# power_supplies.net
KiCad netlist of a schematic drawn in Altium Designer
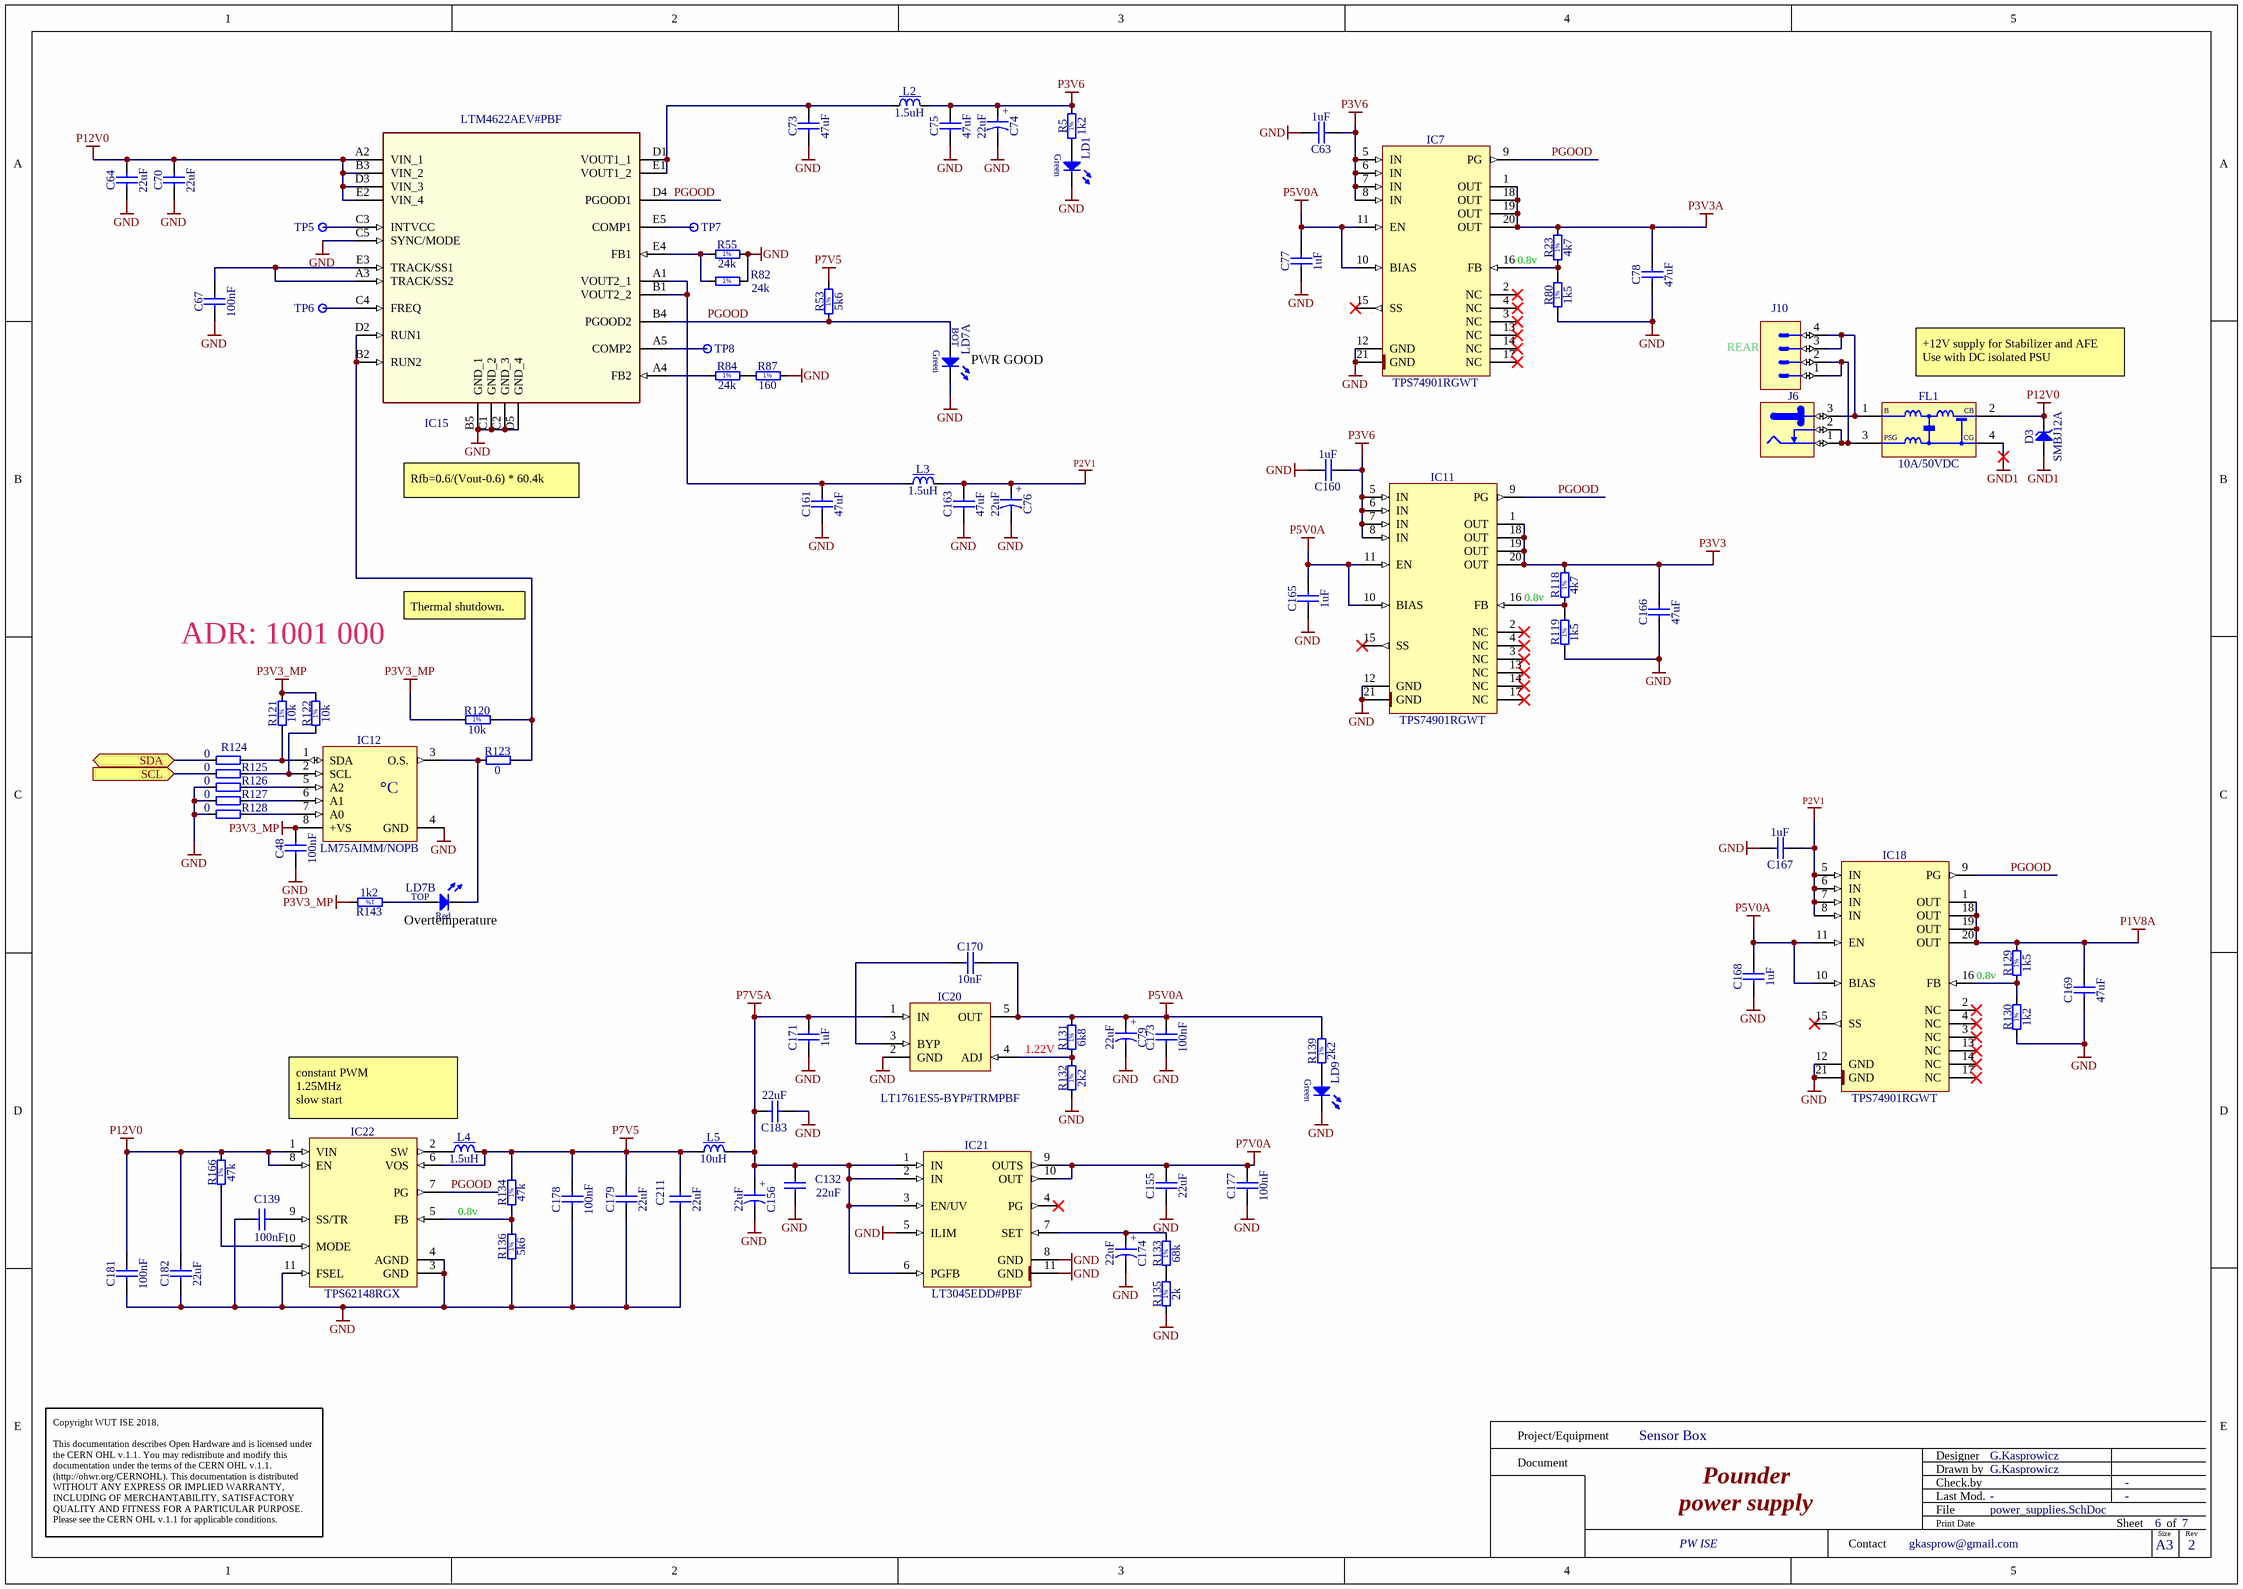
[diagram p0: power_supplies.SchDoc]

(export (version "E")
  (design (tool "Eeschema 10.0.6"))
  (components
    (comp (ref "C48")
      (value "100nF")
      (footprint "CAPC1005X55N")
      (description "Non-polarised capacitor")
      (fields (field (name "PART NUMBER") "CC0402_100NF_16V_10%_X5R") (field (name "VOLTAGE") "16V"))
      (libsource (lib "Capacitors") (part "Capacitor - non polarized"))
    )
    (comp (ref "C63")
      (value "1uF")
      (footprint "CAPC1005X55N")
      (description "Non-polarised capacitor")
      (fields (field (name "PART NUMBER") "CC0402_1UF_16V_10%_X5R") (field (name "VOLTAGE") "16V"))
      (libsource (lib "Capacitors") (part "Capacitor - non polarized"))
    )
    (comp (ref "C64")
      (value "22uF")
      (footprint "CAPC2012X135N")
      (description "Non-polarised capacitor")
      (fields (field (name "PART NUMBER") "CC0805_22UF_16V_10%_X5R") (field (name "VOLTAGE") "16V"))
      (libsource (lib "Capacitors") (part "Capacitor - non polarized"))
    )
    (comp (ref "C67")
      (value "100nF")
      (footprint "CAPC1005X55N")
      (description "Non-polarised capacitor")
      (fields (field (name "PART NUMBER") "CC0402_100NF_16V_10%_X5R") (field (name "VOLTAGE") "16V"))
      (libsource (lib "Capacitors") (part "Capacitor - non polarized"))
    )
    (comp (ref "C70")
      (value "22uF")
      (footprint "CAPC2012X135N")
      (description "Non-polarised capacitor")
      (fields (field (name "PART NUMBER") "CC0805_22UF_16V_10%_X5R") (field (name "VOLTAGE") "16V"))
      (libsource (lib "Capacitors") (part "Capacitor - non polarized"))
    )
    (comp (ref "C73")
      (value "47uF")
      (footprint "CAPC3225X270N")
      (description "Non-polarised capacitor")
      (fields (field (name "PART NUMBER") "CC1210_47UF_10V_20%_X5R") (field (name "VOLTAGE") "10V"))
      (libsource (lib "Capacitors") (part "Capacitor - non polarized"))
    )
    (comp (ref "C74")
      (value "22uF")
      (footprint "CAPMP3528X210N")
      (description "Polarised capacitor")
      (fields (field (name "PART NUMBER") "CTE3528-21_22UF_10V_10%_LESR0700") (field (name "VOLTAGE") "10V"))
      (libsource (lib "Capacitors") (part "Capacitor - polarized"))
    )
    (comp (ref "C75")
      (value "47uF")
      (footprint "CAPC3225X270N")
      (description "Non-polarised capacitor")
      (fields (field (name "PART NUMBER") "CC1210_47UF_10V_20%_X5R") (field (name "VOLTAGE") "10V"))
      (libsource (lib "Capacitors") (part "Capacitor - non polarized"))
    )
    (comp (ref "C76")
      (value "22uF")
      (footprint "CAPMP3528X210N")
      (description "Polarised capacitor")
      (fields (field (name "PART NUMBER") "CTE3528-21_22UF_10V_10%_LESR0700") (field (name "VOLTAGE") "10V"))
      (libsource (lib "Capacitors") (part "Capacitor - polarized"))
    )
    (comp (ref "C77")
      (value "1uF")
      (footprint "CAPC1005X55N")
      (description "Non-polarised capacitor")
      (fields (field (name "PART NUMBER") "CC0402_1UF_16V_10%_X5R") (field (name "VOLTAGE") "16V"))
      (libsource (lib "Capacitors") (part "Capacitor - non polarized"))
    )
    (comp (ref "C78")
      (value "47uF")
      (footprint "CAPC3225X270N")
      (description "Non-polarised capacitor")
      (fields (field (name "PART NUMBER") "CC1210_47UF_10V_20%_X5R") (field (name "VOLTAGE") "10V"))
      (libsource (lib "Capacitors") (part "Capacitor - non polarized"))
    )
    (comp (ref "C79")
      (value "22uF")
      (footprint "CAPMP3528X210N")
      (description "Polarised capacitor")
      (fields (field (name "PART NUMBER") "CTE3528-21_22UF_10V_10%_LESR0700") (field (name "VOLTAGE") "10V"))
      (libsource (lib "Capacitors") (part "Capacitor - polarized"))
    )
    (comp (ref "C132")
      (value "22uF")
      (footprint "CAPC2012X135N")
      (description "Non-polarised capacitor")
      (fields (field (name "PART NUMBER") "CC0805_22UF_16V_10%_X5R") (field (name "VOLTAGE") "16V"))
      (libsource (lib "Capacitors") (part "Capacitor - non polarized"))
    )
    (comp (ref "C139")
      (value "100nF")
      (footprint "CAPC1005X55N")
      (description "Non-polarised capacitor")
      (fields (field (name "PART NUMBER") "CC0402_100NF_16V_10%_X5R") (field (name "VOLTAGE") "16V"))
      (libsource (lib "Capacitors") (part "Capacitor - non polarized"))
    )
    (comp (ref "C155")
      (value "22uF")
      (footprint "CAPC2012X135N")
      (description "Non-polarised capacitor")
      (fields (field (name "PART NUMBER") "CC0805_22UF_16V_10%_X5R") (field (name "VOLTAGE") "16V"))
      (libsource (lib "Capacitors") (part "Capacitor - non polarized"))
    )
    (comp (ref "C156")
      (value "22uF")
      (footprint "CAPMP3528X210N")
      (description "Polarised capacitor")
      (fields (field (name "PART NUMBER") "CTE3528-21_22UF_10V_10%_LESR0700") (field (name "VOLTAGE") "10V"))
      (libsource (lib "Capacitors") (part "Capacitor - polarized"))
    )
    (comp (ref "C160")
      (value "1uF")
      (footprint "CAPC1005X55N")
      (description "Non-polarised capacitor")
      (fields (field (name "PART NUMBER") "CC0402_1UF_16V_10%_X5R") (field (name "VOLTAGE") "16V"))
      (libsource (lib "Capacitors") (part "Capacitor - non polarized"))
    )
    (comp (ref "C161")
      (value "47uF")
      (footprint "CAPC3225X270N")
      (description "Non-polarised capacitor")
      (fields (field (name "PART NUMBER") "CC1210_47UF_10V_20%_X5R") (field (name "VOLTAGE") "10V"))
      (libsource (lib "Capacitors") (part "Capacitor - non polarized"))
    )
    (comp (ref "C163")
      (value "47uF")
      (footprint "CAPC3225X270N")
      (description "Non-polarised capacitor")
      (fields (field (name "PART NUMBER") "CC1210_47UF_10V_20%_X5R") (field (name "VOLTAGE") "10V"))
      (libsource (lib "Capacitors") (part "Capacitor - non polarized"))
    )
    (comp (ref "C165")
      (value "1uF")
      (footprint "CAPC1005X55N")
      (description "Non-polarised capacitor")
      (fields (field (name "PART NUMBER") "CC0402_1UF_16V_10%_X5R") (field (name "VOLTAGE") "16V"))
      (libsource (lib "Capacitors") (part "Capacitor - non polarized"))
    )
    (comp (ref "C166")
      (value "47uF")
      (footprint "CAPC3225X270N")
      (description "Non-polarised capacitor")
      (fields (field (name "PART NUMBER") "CC1210_47UF_10V_20%_X5R") (field (name "VOLTAGE") "10V"))
      (libsource (lib "Capacitors") (part "Capacitor - non polarized"))
    )
    (comp (ref "C167")
      (value "1uF")
      (footprint "CAPC1005X55N")
      (description "Non-polarised capacitor")
      (fields (field (name "PART NUMBER") "CC0402_1UF_16V_10%_X5R") (field (name "VOLTAGE") "16V"))
      (libsource (lib "Capacitors") (part "Capacitor - non polarized"))
    )
    (comp (ref "C168")
      (value "1uF")
      (footprint "CAPC1005X55N")
      (description "Non-polarised capacitor")
      (fields (field (name "PART NUMBER") "CC0402_1UF_16V_10%_X5R") (field (name "VOLTAGE") "16V"))
      (libsource (lib "Capacitors") (part "Capacitor - non polarized"))
    )
    (comp (ref "C169")
      (value "47uF")
      (footprint "CAPC3225X270N")
      (description "Non-polarised capacitor")
      (fields (field (name "PART NUMBER") "CC1210_47UF_10V_20%_X5R") (field (name "VOLTAGE") "10V"))
      (libsource (lib "Capacitors") (part "Capacitor - non polarized"))
    )
    (comp (ref "C170")
      (value "10nF")
      (footprint "CAPC1005X55N")
      (description "Non-polarised capacitor")
      (fields (field (name "PART NUMBER") "CC0402_10NF_16V_10%_X7R") (field (name "VOLTAGE") "16V"))
      (libsource (lib "Capacitors") (part "Capacitor - non polarized"))
    )
    (comp (ref "C171")
      (value "1uF")
      (footprint "CAPC1005X55N")
      (description "Non-polarised capacitor")
      (fields (field (name "PART NUMBER") "CC0402_1UF_16V_10%_X5R") (field (name "VOLTAGE") "16V"))
      (libsource (lib "Capacitors") (part "Capacitor - non polarized"))
    )
    (comp (ref "C173")
      (value "100nF")
      (footprint "CAPC1005X55N")
      (description "Non-polarised capacitor")
      (fields (field (name "PART NUMBER") "CC0402_100NF_16V_10%_X5R") (field (name "VOLTAGE") "16V"))
      (libsource (lib "Capacitors") (part "Capacitor - non polarized"))
    )
    (comp (ref "C174")
      (value "22uF")
      (footprint "CAPMP3528X210N")
      (description "Polarised capacitor")
      (fields (field (name "PART NUMBER") "CTE3528-21_22UF_10V_10%_LESR0700") (field (name "VOLTAGE") "10V"))
      (libsource (lib "Capacitors") (part "Capacitor - polarized"))
    )
    (comp (ref "C177")
      (value "100nF")
      (footprint "CAPC1005X55N")
      (description "Non-polarised capacitor")
      (fields (field (name "PART NUMBER") "CC0402_100NF_16V_10%_X5R") (field (name "VOLTAGE") "16V"))
      (libsource (lib "Capacitors") (part "Capacitor - non polarized"))
    )
    (comp (ref "C178")
      (value "100nF")
      (footprint "CAPC1005X55N")
      (description "Non-polarised capacitor")
      (fields (field (name "PART NUMBER") "CC0402_100NF_16V_10%_X5R") (field (name "VOLTAGE") "16V"))
      (libsource (lib "Capacitors") (part "Capacitor - non polarized"))
    )
    (comp (ref "C179")
      (value "22uF")
      (footprint "CAPC2012X135N")
      (description "Non-polarised capacitor")
      (fields (field (name "PART NUMBER") "CC0805_22UF_16V_10%_X5R") (field (name "VOLTAGE") "16V"))
      (libsource (lib "Capacitors") (part "Capacitor - non polarized"))
    )
    (comp (ref "C181")
      (value "100nF")
      (footprint "CAPC1005X55N")
      (description "Non-polarised capacitor")
      (fields (field (name "PART NUMBER") "CC0402_100NF_16V_10%_X5R") (field (name "VOLTAGE") "16V"))
      (libsource (lib "Capacitors") (part "Capacitor - non polarized"))
    )
    (comp (ref "C182")
      (value "22uF")
      (footprint "CAPC2012X135N")
      (description "Non-polarised capacitor")
      (fields (field (name "PART NUMBER") "CC0805_22UF_16V_10%_X5R") (field (name "VOLTAGE") "16V"))
      (libsource (lib "Capacitors") (part "Capacitor - non polarized"))
    )
    (comp (ref "C183")
      (value "22uF")
      (footprint "CAPC2012X135N")
      (description "Non-polarised capacitor")
      (fields (field (name "PART NUMBER") "CC0805_22UF_16V_10%_X5R") (field (name "VOLTAGE") "16V"))
      (libsource (lib "Capacitors") (part "Capacitor - non polarized"))
    )
    (comp (ref "C211")
      (value "22uF")
      (footprint "CAPC2012X135N")
      (description "Non-polarised capacitor")
      (fields (field (name "PART NUMBER") "CC0805_22UF_16V_10%_X5R") (field (name "VOLTAGE") "16V"))
      (libsource (lib "Capacitors") (part "Capacitor - non polarized"))
    )
    (comp (ref "D3")
      (value "SMBJ12A")
      (footprint "DIOM5336X265N")
      (description "Zener Diode")
      (fields (field (name "VOLTAGE") "12V") (field (name "POWER") "600W"))
      (libsource (lib "ICs And Semiconductors") (part "Diode Zener"))
    )
    (comp (ref "FL1")
      (value "10A/50VDC")
      (footprint "FIL_MURATA_BNX02")
      (description "Block Type EMIFIL (LC Combined)")
      (fields (field (name "PART NUMBER") "FIL_MURATA_BNX022-01L") (field (name "MANUFACTURER") "MURATA"))
      (libsource (lib "Inductors & Transformers") (part "FIL_MURATA_BNX02"))
    )
    (comp (ref "IC7")
      (value "TPS74901RGWT")
      (footprint "QFN65P500X500X100-21N-S325")
      (description "3A, 0.8 to 3.6V Adjustable Low-Dropout Linear Regulator with Programmable Soft-Start")
      (fields (field (name "MANUFACTURER") "TEXAS INSTRUMENTS"))
      (libsource (lib "ICs And Semiconductors") (part "TPS74901RGWT"))
    )
    (comp (ref "IC11")
      (value "TPS74901RGWT")
      (footprint "QFN65P500X500X100-21N-S325")
      (description "3A, 0.8 to 3.6V Adjustable Low-Dropout Linear Regulator with Programmable Soft-Start")
      (fields (field (name "MANUFACTURER") "TEXAS INSTRUMENTS"))
      (libsource (lib "ICs And Semiconductors") (part "TPS74901RGWT"))
    )
    (comp (ref "IC12")
      (value "LM75AIMM/NOPB")
      (footprint "SOP65P490X109-8N")
      (description "Digital Temperature Sensor and Thermal Watchdog with Two-Wire Interface")
      (fields (field (name "MANUFACTURER") "TEXAS INSTRUMENTS"))
      (libsource (lib "ICs And Semiconductors") (part "LM75"))
    )
    (comp (ref "IC15")
      (value "LTM4622AEV#PBF")
      (footprint "LGA25C127P5X5_625X625X190")
      (description "Dual Ultrathin 2A or Single 4A, 3.6V to 20V, 1.5V to 12V   Step-Down DC/DC μModule Regulator")
      (fields (field (name "MANUFACTURER") "LINEAR TECHNOLOGY"))
      (libsource (lib "LIBRARY_SCH") (part "PM_LTM4622"))
    )
    (comp (ref "IC18")
      (value "TPS74901RGWT")
      (footprint "QFN65P500X500X100-21N-S325")
      (description "3A, 0.8 to 3.6V Adjustable Low-Dropout Linear Regulator with Programmable Soft-Start")
      (fields (field (name "MANUFACTURER") "TEXAS INSTRUMENTS"))
      (libsource (lib "ICs And Semiconductors") (part "TPS74901RGWT"))
    )
    (comp (ref "IC20")
      (value "LT1761ES5-BYP#TRMPBF")
      (footprint "SOT95P280X100-5N")
      (description "100mA, Low Noise, LDO Micropower Adjustable Regulator in SOT-23")
      (fields (field (name "MANUFACTURER") "LINEAR TECHNOLOGY"))
      (libsource (lib "ICs And Semiconductors") (part "LT1761-BYP"))
    )
    (comp (ref "IC21")
      (value "LT3045EDD#PBF")
      (footprint "SON50P300X300X80-11N-R175X248")
      (description "20V, 500mA, Ultralow Noise, Ultrahigh PSRR Linear Regulator")
      (fields (field (name "MANUFACTURER") "LINEAR TECHNOLOGY"))
      (libsource (lib "ICs And Semiconductors") (part "LT3045EDD"))
    )
    (comp (ref "IC22")
      (value "TPS62148RGX")
      (footprint "TEXAS_RGX0011A")
      (description "3V-17V 2A Step-Down Converter, High Accuracy, With DCS-Control")
      (fields (field (name "MANUFACTURER") "TEXAS INSTRUMENTS"))
      (libsource (lib "ICs And Semiconductors") (part "TPS62148"))
    )
    (comp (ref "J6")
      (value "Jack")
      (footprint "Library-connectors:SWITCHCRAFT_L712RA")
      (description "24V /3. 5A, 2.1mm Diameter Pin, SMD DC Power Supply Connector With  Break Contact")
      (fields (field (name "PART NUMBER") "SWITCHCRAFT_L712RA") (field (name "MANUFACTURER") "SWITCHCRAFT"))
      (libsource (lib "LIBRARY_SCH") (part "CON_DC_5A_THT_RA"))
    )
    (comp (ref "J10")
      (value "Mini-Fit Jr.™")
      (footprint "MOLEX_39-30-0040")
      (description "Connector 4 Male")
      (fields (field (name "PART NUMBER") "MOLEX_39-30-0040") (field (name "MANUFACTURER") "MOLEX"))
      (libsource (lib "Connectors") (part "Connector 4 Male"))
    )
    (comp (ref "L2")
      (value "1.5uH")
      (footprint "IND_TDK_SPM6530")
      (description "Inductor With Core")
      (fields (field (name "PART NUMBER") "IND_1.5UH_20%_TDK_SPM6530") (field (name "POWER") "11A"))
      (libsource (lib "Inductors & Transformers") (part "Inductor With Magnetic core"))
    )
    (comp (ref "L3")
      (value "1.5uH")
      (footprint "IND_TDK_SPM6530")
      (description "Inductor With Core")
      (fields (field (name "PART NUMBER") "IND_1.5UH_20%_TDK_SPM6530") (field (name "POWER") "11A"))
      (libsource (lib "Inductors & Transformers") (part "Inductor With Magnetic core"))
    )
    (comp (ref "L4")
      (value "1.5uH")
      (footprint "IND_TDK_SPM6530")
      (description "Inductor With Core")
      (fields (field (name "PART NUMBER") "IND_1.5UH_20%_TDK_SPM6530") (field (name "POWER") "11A"))
      (libsource (lib "Inductors & Transformers") (part "Inductor With Magnetic core"))
    )
    (comp (ref "L5")
      (value "10uH")
      (footprint "IND_MURATA-PS_8400")
      (description "Inductor With Core")
      (fields (field (name "PART NUMBER") "IND_10UH_10%_MURATA-PS_8400") (field (name "POWER") "950mA"))
      (libsource (lib "Inductors & Transformers") (part "Inductor With Magnetic core"))
    )
    (comp (ref "LD1")
      (value "Green")
      (footprint "LED_KINGBRIGHT_KPH-1608CGCKr")
      (description "Green 0603")
      (fields
        (field (name "PART NUMBER") "LED_KINGBRIGHT_KPH-1608CGCK")
        (field (name "MANUFACTURER") "KINGBRIGHT")
      )
      (libsource (lib "LIBRARY_SCH") (part "LED_0603_Green"))
    )
    (comp (ref "LD7")
      (value "Red/Green")
      (footprint "LED_DIALIGHT_571-0112F")
      (description "2x LED  Botom Green, Top Red")
      (fields (field (name "PART NUMBER") "LED_DIALIGHT_571-0112F") (field (name "MANUFACTURER") "DIALIGHT"))
      (libsource (lib "ICs And Semiconductors") (part "LED x2 G-1C2A-BOT_R-3C4A-TOP"))
    )
    (comp (ref "LD9")
      (value "Green")
      (footprint "LED_KINGBRIGHT_KPH-1608CGCKr")
      (description "Green 0603")
      (fields
        (field (name "PART NUMBER") "LED_KINGBRIGHT_KPH-1608CGCK")
        (field (name "MANUFACTURER") "KINGBRIGHT")
      )
      (libsource (lib "LIBRARY_SCH") (part "LED_0603_Green"))
    )
    (comp (ref "R5")
      (value "1k2")
      (footprint "RESC1608X55N")
      (description "Resistor - 1%")
      (fields (field (name "PART NUMBER") "R0603_1K2_1%_0.1W_100PPM") (field (name "POWER") "0.1W"))
      (libsource (lib "Resistors") (part "Resistor - 1%"))
    )
    (comp (ref "R23")
      (value "4k7")
      (footprint "RESC1608X55N")
      (description "Resistor - 1%")
      (fields (field (name "PART NUMBER") "R0603_4K7_1%_0.1W_100PPM") (field (name "POWER") "0.1W"))
      (libsource (lib "Resistors") (part "Resistor - 1%"))
    )
    (comp (ref "R53")
      (value "5k6")
      (footprint "RESC1608X55N")
      (description "Resistor - 1%")
      (fields (field (name "PART NUMBER") "R0603_5K6_1%_0.1W_100PPM") (field (name "POWER") "0.1W"))
      (libsource (lib "Resistors") (part "Resistor - 1%"))
    )
    (comp (ref "R55")
      (value "24k")
      (footprint "RESC1608X55N")
      (description "Resistor - 1%")
      (fields (field (name "PART NUMBER") "R0603_24K_1%_0.1W_100PPM") (field (name "POWER") "0.1W"))
      (libsource (lib "Resistors") (part "Resistor - 1%"))
    )
    (comp (ref "R80")
      (value "1k5")
      (footprint "RESC1608X55N")
      (description "Resistor - 1%")
      (fields (field (name "PART NUMBER") "R0603_1K5_1%_0.1W_100PPM") (field (name "POWER") "0.1W"))
      (libsource (lib "Resistors") (part "Resistor - 1%"))
    )
    (comp (ref "R82")
      (value "24k")
      (footprint "RESC1608X55N")
      (description "Resistor - 1%")
      (fields (field (name "PART NUMBER") "R0603_24K_1%_0.1W_100PPM") (field (name "POWER") "0.1W"))
      (libsource (lib "Resistors") (part "Resistor - 1%"))
    )
    (comp (ref "R84")
      (value "24k")
      (footprint "RESC1608X55N")
      (description "Resistor - 1%")
      (fields (field (name "PART NUMBER") "R0603_24K_1%_0.1W_100PPM") (field (name "POWER") "0.1W"))
      (libsource (lib "Resistors") (part "Resistor - 1%"))
    )
    (comp (ref "R87")
      (value "160")
      (footprint "RESC1608X55N")
      (description "Resistor - 1%")
      (fields (field (name "PART NUMBER") "R0603_160R_1%_0.1W_100PPM") (field (name "POWER") "0.1W"))
      (libsource (lib "Resistors") (part "Resistor - 1%"))
    )
    (comp (ref "R118")
      (value "4k7")
      (footprint "RESC1608X55N")
      (description "Resistor - 1%")
      (fields (field (name "PART NUMBER") "R0603_4K7_1%_0.1W_100PPM") (field (name "POWER") "0.1W"))
      (libsource (lib "Resistors") (part "Resistor - 1%"))
    )
    (comp (ref "R119")
      (value "1k5")
      (footprint "RESC1608X55N")
      (description "Resistor - 1%")
      (fields (field (name "PART NUMBER") "R0603_1K5_1%_0.1W_100PPM") (field (name "POWER") "0.1W"))
      (libsource (lib "Resistors") (part "Resistor - 1%"))
    )
    (comp (ref "R120")
      (value "10k")
      (footprint "RESC1005X40N")
      (description "Resistor - 1%")
      (fields (field (name "PART NUMBER") "R0402_10K_1%_0.0625W_100PPM") (field (name "POWER") "0.0625W"))
      (libsource (lib "Resistors") (part "Resistor - 1%"))
    )
    (comp (ref "R121")
      (value "10k")
      (footprint "RESC1005X40N")
      (description "Resistor - 1%")
      (fields (field (name "PART NUMBER") "R0402_10K_1%_0.0625W_100PPM") (field (name "POWER") "0.0625W"))
      (libsource (lib "Resistors") (part "Resistor - 1%"))
    )
    (comp (ref "R122")
      (value "10k")
      (footprint "RESC1005X40N")
      (description "Resistor - 1%")
      (fields (field (name "PART NUMBER") "R0402_10K_1%_0.0625W_100PPM") (field (name "POWER") "0.0625W"))
      (libsource (lib "Resistors") (part "Resistor - 1%"))
    )
    (comp (ref "R123")
      (value "0")
      (footprint "RESC1005X40N")
      (description "Resistor")
      (fields (field (name "PART NUMBER") "R0402_0R_JUMPER") (field (name "MANUFACTURER") "GENERIC"))
      (libsource (lib "Resistors") (part "Resistor"))
    )
    (comp (ref "R124")
      (value "0")
      (footprint "RESC1005X40N")
      (description "Resistor")
      (fields (field (name "PART NUMBER") "R0402_0R_JUMPER") (field (name "MANUFACTURER") "GENERIC"))
      (libsource (lib "Resistors") (part "Resistor"))
    )
    (comp (ref "R125")
      (value "0")
      (footprint "RESC1005X40N")
      (description "Resistor")
      (fields (field (name "PART NUMBER") "R0402_0R_JUMPER") (field (name "MANUFACTURER") "GENERIC"))
      (libsource (lib "Resistors") (part "Resistor"))
    )
    (comp (ref "R126")
      (value "0")
      (footprint "RESC1005X40N")
      (description "Resistor")
      (fields (field (name "PART NUMBER") "R0402_0R_JUMPER") (field (name "MANUFACTURER") "GENERIC"))
      (libsource (lib "Resistors") (part "Resistor"))
    )
    (comp (ref "R127")
      (value "0")
      (footprint "RESC1005X40N")
      (description "Resistor")
      (fields (field (name "PART NUMBER") "R0402_0R_JUMPER") (field (name "MANUFACTURER") "GENERIC"))
      (libsource (lib "Resistors") (part "Resistor"))
    )
    (comp (ref "R128")
      (value "0")
      (footprint "RESC1005X40N")
      (description "Resistor")
      (fields (field (name "PART NUMBER") "R0402_0R_JUMPER") (field (name "MANUFACTURER") "GENERIC"))
      (libsource (lib "Resistors") (part "Resistor"))
    )
    (comp (ref "R129")
      (value "1k5")
      (footprint "RESC1608X55N")
      (description "Resistor - 1%")
      (fields (field (name "PART NUMBER") "R0603_1K5_1%_0.1W_100PPM") (field (name "POWER") "0.1W"))
      (libsource (lib "Resistors") (part "Resistor - 1%"))
    )
    (comp (ref "R130")
      (value "1k2")
      (footprint "RESC1608X55N")
      (description "Resistor - 1%")
      (fields (field (name "PART NUMBER") "R0603_1K2_1%_0.1W_100PPM") (field (name "POWER") "0.1W"))
      (libsource (lib "Resistors") (part "Resistor - 1%"))
    )
    (comp (ref "R131")
      (value "6k8")
      (footprint "RESC1608X55N")
      (description "Resistor - 1%")
      (fields (field (name "PART NUMBER") "R0603_6K8_1%_0.1W_100PPM") (field (name "POWER") "0.1W"))
      (libsource (lib "Resistors") (part "Resistor - 1%"))
    )
    (comp (ref "R132")
      (value "2k2")
      (footprint "RESC1608X55N")
      (description "Resistor - 1%")
      (fields (field (name "PART NUMBER") "R0603_2K2_1%_0.1W_100PPM") (field (name "POWER") "0.1W"))
      (libsource (lib "Resistors") (part "Resistor - 1%"))
    )
    (comp (ref "R133")
      (value "68k")
      (footprint "RESC1005X40N")
      (description "Resistor - 1%")
      (fields (field (name "PART NUMBER") "R0402_68K_1%_0.0625W_100PPM") (field (name "POWER") "0.0625W"))
      (libsource (lib "Resistors") (part "Resistor - 1%"))
    )
    (comp (ref "R134")
      (value "47k")
      (footprint "RESC1608X55N")
      (description "Resistor - 1%")
      (fields (field (name "PART NUMBER") "R0603_47K_1%_0.1W_100PPM") (field (name "POWER") "0.1W"))
      (libsource (lib "Resistors") (part "Resistor - 1%"))
    )
    (comp (ref "R135")
      (value "2k")
      (footprint "RESC1005X40N")
      (description "Resistor - 1%")
      (fields (field (name "PART NUMBER") "R0402_2K_1%_0.0625W_100PPM") (field (name "POWER") "0.0625W"))
      (libsource (lib "Resistors") (part "Resistor - 1%"))
    )
    (comp (ref "R136")
      (value "5k6")
      (footprint "RESC1608X55N")
      (description "Resistor - 1%")
      (fields (field (name "PART NUMBER") "R0603_5K6_1%_0.1W_100PPM") (field (name "POWER") "0.1W"))
      (libsource (lib "Resistors") (part "Resistor - 1%"))
    )
    (comp (ref "R139")
      (value "2k2")
      (footprint "RESC1608X55N")
      (description "Resistor - 1%")
      (fields (field (name "PART NUMBER") "R0603_2K2_1%_0.1W_100PPM") (field (name "POWER") "0.1W"))
      (libsource (lib "Resistors") (part "Resistor - 1%"))
    )
    (comp (ref "R143")
      (value "1k2")
      (footprint "RESC1608X55N")
      (description "Resistor - 1%")
      (fields (field (name "PART NUMBER") "R0603_1K2_1%_0.1W_100PPM") (field (name "POWER") "0.1W"))
      (libsource (lib "Resistors") (part "Resistor - 1%"))
    )
    (comp (ref "R166")
      (value "47k")
      (footprint "RESC1608X55N")
      (description "Resistor - 1%")
      (fields (field (name "PART NUMBER") "R0603_47K_1%_0.1W_100PPM") (field (name "POWER") "0.1W"))
      (libsource (lib "Resistors") (part "Resistor - 1%"))
    )
    (comp (ref "TP5")
      (value "Test Point")
      (footprint "TPS127")
      (fields (field (name "PART NUMBER") "SMD_PAD_1.27X1.27MM"))
      (libsource (lib "Eletro-mechanical") (part "Test Point"))
    )
    (comp (ref "TP6")
      (value "Test Point")
      (footprint "TPS127")
      (fields (field (name "PART NUMBER") "SMD_PAD_1.27X1.27MM"))
      (libsource (lib "Eletro-mechanical") (part "Test Point"))
    )
    (comp (ref "TP7")
      (value "Test Point")
      (footprint "TPS127")
      (fields (field (name "PART NUMBER") "SMD_PAD_1.27X1.27MM"))
      (libsource (lib "Eletro-mechanical") (part "Test Point"))
    )
    (comp (ref "TP8")
      (value "Test Point")
      (footprint "TPS127")
      (fields (field (name "PART NUMBER") "SMD_PAD_1.27X1.27MM"))
      (libsource (lib "Eletro-mechanical") (part "Test Point"))
    )
  )
  (nets
    (net (code "1") (name "/PGOOD") (class "Default")
      (node (ref "IC11") (pin "9") (pinfunction "PG_9") (pintype "output"))
      (node (ref "IC15") (pin "B4") (pinfunction "PGOOD2_B4") (pintype "open_collector"))
      (node (ref "IC15") (pin "D4") (pinfunction "PGOOD1_D4") (pintype "open_collector"))
      (node (ref "IC18") (pin "9") (pinfunction "PG_9") (pintype "output"))
      (node (ref "IC22") (pin "7") (pinfunction "PG_7") (pintype "output"))
      (node (ref "IC7") (pin "9") (pinfunction "PG_9") (pintype "output"))
      (node (ref "LD7") (pin "2") (pinfunction "A_2") (pintype "passive"))
      (node (ref "R53") (pin "1") (pinfunction "1_1") (pintype "passive"))
    )
    (net (code "2") (name "/SCL") (class "Default")
      (node (ref "R125") (pin "1") (pinfunction "1_1") (pintype "passive"))
    )
    (net (code "3") (name "/SDA") (class "Default")
      (node (ref "R124") (pin "1") (pinfunction "1_1") (pintype "passive"))
    )
    (net (code "4") (name "GND") (class "Default")
      (node (ref "C132") (pin "1") (pinfunction "1_1") (pintype "passive"))
      (node (ref "C139") (pin "2") (pinfunction "2_2") (pintype "passive"))
      (node (ref "C155") (pin "1") (pinfunction "1_1") (pintype "passive"))
      (node (ref "C156") (pin "2") (pinfunction "2_2") (pintype "passive"))
      (node (ref "C160") (pin "2") (pinfunction "2_2") (pintype "passive"))
      (node (ref "C161") (pin "1") (pinfunction "1_1") (pintype "passive"))
      (node (ref "C163") (pin "1") (pinfunction "1_1") (pintype "passive"))
      (node (ref "C165") (pin "1") (pinfunction "1_1") (pintype "passive"))
      (node (ref "C166") (pin "1") (pinfunction "1_1") (pintype "passive"))
      (node (ref "C167") (pin "2") (pinfunction "2_2") (pintype "passive"))
      (node (ref "C168") (pin "1") (pinfunction "1_1") (pintype "passive"))
      (node (ref "C169") (pin "1") (pinfunction "1_1") (pintype "passive"))
      (node (ref "C171") (pin "1") (pinfunction "1_1") (pintype "passive"))
      (node (ref "C173") (pin "1") (pinfunction "1_1") (pintype "passive"))
      (node (ref "C174") (pin "2") (pinfunction "2_2") (pintype "passive"))
      (node (ref "C177") (pin "1") (pinfunction "1_1") (pintype "passive"))
      (node (ref "C178") (pin "1") (pinfunction "1_1") (pintype "passive"))
      (node (ref "C179") (pin "1") (pinfunction "1_1") (pintype "passive"))
      (node (ref "C181") (pin "1") (pinfunction "1_1") (pintype "passive"))
      (node (ref "C182") (pin "1") (pinfunction "1_1") (pintype "passive"))
      (node (ref "C183") (pin "1") (pinfunction "1_1") (pintype "passive"))
      (node (ref "C211") (pin "1") (pinfunction "1_1") (pintype "passive"))
      (node (ref "C48") (pin "1") (pinfunction "1_1") (pintype "passive"))
      (node (ref "C63") (pin "2") (pinfunction "2_2") (pintype "passive"))
      (node (ref "C64") (pin "1") (pinfunction "1_1") (pintype "passive"))
      (node (ref "C67") (pin "1") (pinfunction "1_1") (pintype "passive"))
      (node (ref "C70") (pin "1") (pinfunction "1_1") (pintype "passive"))
      (node (ref "C73") (pin "1") (pinfunction "1_1") (pintype "passive"))
      (node (ref "C74") (pin "2") (pinfunction "2_2") (pintype "passive"))
      (node (ref "C75") (pin "1") (pinfunction "1_1") (pintype "passive"))
      (node (ref "C76") (pin "2") (pinfunction "2_2") (pintype "passive"))
      (node (ref "C77") (pin "1") (pinfunction "1_1") (pintype "passive"))
      (node (ref "C78") (pin "1") (pinfunction "1_1") (pintype "passive"))
      (node (ref "C79") (pin "2") (pinfunction "2_2") (pintype "passive"))
      (node (ref "IC11") (pin "12") (pinfunction "GND_12") (pintype "power_in"))
      (node (ref "IC11") (pin "21") (pinfunction "GND_21") (pintype "power_in"))
      (node (ref "IC12") (pin "4") (pinfunction "GND_4") (pintype "power_in"))
      (node (ref "IC15") (pin "B5") (pinfunction "GND_1_B5") (pintype "power_in"))
      (node (ref "IC15") (pin "C1") (pinfunction "GND_2_C1") (pintype "power_in"))
      (node (ref "IC15") (pin "C2") (pinfunction "GND_3_C2") (pintype "power_in"))
      (node (ref "IC15") (pin "C5") (pinfunction "SYNC/MODE_C5") (pintype "input"))
      (node (ref "IC15") (pin "D5") (pinfunction "GND_4_D5") (pintype "power_in"))
      (node (ref "IC18") (pin "12") (pinfunction "GND_12") (pintype "power_in"))
      (node (ref "IC18") (pin "21") (pinfunction "GND_21") (pintype "power_in"))
      (node (ref "IC20") (pin "2") (pinfunction "GND_2") (pintype "power_in"))
      (node (ref "IC21") (pin "11") (pinfunction "GND_11") (pintype "power_in"))
      (node (ref "IC21") (pin "5") (pinfunction "ILIM_5") (pintype "input"))
      (node (ref "IC21") (pin "8") (pinfunction "GND_8") (pintype "power_in"))
      (node (ref "IC22") (pin "11") (pinfunction "FSEL_11") (pintype "input"))
      (node (ref "IC22") (pin "3") (pinfunction "GND_3") (pintype "power_in"))
      (node (ref "IC22") (pin "4") (pinfunction "AGND_4") (pintype "power_in"))
      (node (ref "IC7") (pin "12") (pinfunction "GND_12") (pintype "power_in"))
      (node (ref "IC7") (pin "21") (pinfunction "GND_21") (pintype "power_in"))
      (node (ref "LD1") (pin "1") (pinfunction "C_1") (pintype "passive"))
      (node (ref "LD7") (pin "1") (pinfunction "C_1") (pintype "passive"))
      (node (ref "LD9") (pin "1") (pinfunction "C_1") (pintype "passive"))
      (node (ref "R119") (pin "1") (pinfunction "1_1") (pintype "passive"))
      (node (ref "R126") (pin "1") (pinfunction "1_1") (pintype "passive"))
      (node (ref "R127") (pin "1") (pinfunction "1_1") (pintype "passive"))
      (node (ref "R128") (pin "1") (pinfunction "1_1") (pintype "passive"))
      (node (ref "R130") (pin "1") (pinfunction "1_1") (pintype "passive"))
      (node (ref "R132") (pin "1") (pinfunction "1_1") (pintype "passive"))
      (node (ref "R135") (pin "1") (pinfunction "1_1") (pintype "passive"))
      (node (ref "R136") (pin "1") (pinfunction "1_1") (pintype "passive"))
      (node (ref "R55") (pin "2") (pinfunction "2_2") (pintype "passive"))
      (node (ref "R80") (pin "1") (pinfunction "1_1") (pintype "passive"))
      (node (ref "R82") (pin "2") (pinfunction "2_2") (pintype "passive"))
      (node (ref "R87") (pin "2") (pinfunction "2_2") (pintype "passive"))
    )
    (net (code "5") (name "GND1") (class "Default")
      (node (ref "D3") (pin "2") (pinfunction "A_2") (pintype "passive"))
      (node (ref "FL1") (pin "4") (pinfunction "CG_4") (pintype "passive"))
    )
    (net (code "6") (name "Net-(FL1-B)") (class "Default")
      (node (ref "FL1") (pin "1") (pinfunction "B_1") (pintype "passive"))
      (node (ref "J10") (pin "3") (pinfunction "3_3") (pintype "bidirectional"))
      (node (ref "J10") (pin "4") (pinfunction "4_4") (pintype "bidirectional"))
      (node (ref "J6") (pin "3") (pinfunction "3_3") (pintype "bidirectional"))
    )
    (net (code "7") (name "Net-(FL1-PSG)") (class "Default")
      (node (ref "FL1") (pin "3") (pinfunction "PSG_3") (pintype "passive"))
      (node (ref "J10") (pin "1") (pinfunction "1_1") (pintype "bidirectional"))
      (node (ref "J10") (pin "2") (pinfunction "2_2") (pintype "bidirectional"))
      (node (ref "J6") (pin "1") (pinfunction "1_1") (pintype "bidirectional"))
      (node (ref "J6") (pin "2") (pinfunction "2_2") (pintype "bidirectional"))
    )
    (net (code "8") (name "Net-(IC7-FB)") (class "Default")
      (node (ref "IC7") (pin "16") (pinfunction "FB_16") (pintype "input"))
      (node (ref "R23") (pin "1") (pinfunction "1_1") (pintype "passive"))
      (node (ref "R80") (pin "2") (pinfunction "2_2") (pintype "passive"))
    )
    (net (code "9") (name "Net-(IC11-FB)") (class "Default")
      (node (ref "IC11") (pin "16") (pinfunction "FB_16") (pintype "input"))
      (node (ref "R118") (pin "1") (pinfunction "1_1") (pintype "passive"))
      (node (ref "R119") (pin "2") (pinfunction "2_2") (pintype "passive"))
    )
    (net (code "10") (name "Net-(IC12-A0)") (class "Default")
      (node (ref "IC12") (pin "7") (pinfunction "A0_7") (pintype "input"))
      (node (ref "R128") (pin "2") (pinfunction "2_2") (pintype "passive"))
    )
    (net (code "11") (name "Net-(IC12-A1)") (class "Default")
      (node (ref "IC12") (pin "6") (pinfunction "A1_6") (pintype "input"))
      (node (ref "R127") (pin "2") (pinfunction "2_2") (pintype "passive"))
    )
    (net (code "12") (name "Net-(IC12-A2)") (class "Default")
      (node (ref "IC12") (pin "5") (pinfunction "A2_5") (pintype "input"))
      (node (ref "R126") (pin "2") (pinfunction "2_2") (pintype "passive"))
    )
    (net (code "13") (name "Net-(IC12-O.S.)") (class "Default")
      (node (ref "IC12") (pin "3") (pinfunction "O.S._3") (pintype "output"))
      (node (ref "LD7") (pin "3") (pinfunction "C_3") (pintype "passive"))
      (node (ref "R123") (pin "1") (pinfunction "1_1") (pintype "passive"))
    )
    (net (code "14") (name "Net-(IC12-SCL)") (class "Default")
      (node (ref "IC12") (pin "2") (pinfunction "SCL_2") (pintype "input"))
      (node (ref "R122") (pin "1") (pinfunction "1_1") (pintype "passive"))
      (node (ref "R125") (pin "2") (pinfunction "2_2") (pintype "passive"))
    )
    (net (code "15") (name "Net-(IC12-SDA)") (class "Default")
      (node (ref "IC12") (pin "1") (pinfunction "SDA_1") (pintype "bidirectional"))
      (node (ref "R121") (pin "1") (pinfunction "1_1") (pintype "passive"))
      (node (ref "R124") (pin "2") (pinfunction "2_2") (pintype "passive"))
    )
    (net (code "16") (name "Net-(IC15-COMP1)") (class "Default")
      (node (ref "IC15") (pin "E5") (pinfunction "COMP1_E5") (pintype "passive"))
      (node (ref "TP7") (pin "1") (pinfunction "1_1") (pintype "bidirectional"))
    )
    (net (code "17") (name "Net-(IC15-COMP2)") (class "Default")
      (node (ref "IC15") (pin "A5") (pinfunction "COMP2_A5") (pintype "passive"))
      (node (ref "TP8") (pin "1") (pinfunction "1_1") (pintype "bidirectional"))
    )
    (net (code "18") (name "Net-(IC15-FB1)") (class "Default")
      (node (ref "IC15") (pin "E4") (pinfunction "FB1_E4") (pintype "input"))
      (node (ref "R55") (pin "1") (pinfunction "1_1") (pintype "passive"))
      (node (ref "R82") (pin "1") (pinfunction "1_1") (pintype "passive"))
    )
    (net (code "19") (name "Net-(IC15-FB2)") (class "Default")
      (node (ref "IC15") (pin "A4") (pinfunction "FB2_A4") (pintype "input"))
      (node (ref "R84") (pin "1") (pinfunction "1_1") (pintype "passive"))
    )
    (net (code "20") (name "Net-(IC15-FREQ)") (class "Default")
      (node (ref "IC15") (pin "C4") (pinfunction "FREQ_C4") (pintype "input"))
      (node (ref "TP6") (pin "1") (pinfunction "1_1") (pintype "bidirectional"))
    )
    (net (code "21") (name "Net-(IC15-INTVCC)") (class "Default")
      (node (ref "IC15") (pin "C3") (pinfunction "INTVCC_C3") (pintype "input"))
      (node (ref "TP5") (pin "1") (pinfunction "1_1") (pintype "bidirectional"))
    )
    (net (code "22") (name "Net-(IC15-RUN1)") (class "Default")
      (node (ref "IC15") (pin "B2") (pinfunction "RUN2_B2") (pintype "input"))
      (node (ref "IC15") (pin "D2") (pinfunction "RUN1_D2") (pintype "input"))
      (node (ref "R120") (pin "2") (pinfunction "2_2") (pintype "passive"))
      (node (ref "R123") (pin "2") (pinfunction "2_2") (pintype "passive"))
    )
    (net (code "23") (name "Net-(IC15-TRACK{slash}SS1)") (class "Default")
      (node (ref "C67") (pin "2") (pinfunction "2_2") (pintype "passive"))
      (node (ref "IC15") (pin "A3") (pinfunction "TRACK/SS2_A3") (pintype "input"))
      (node (ref "IC15") (pin "E3") (pinfunction "TRACK/SS1_E3") (pintype "input"))
    )
    (net (code "24") (name "Net-(IC15-VOUT1_1)") (class "Default")
      (node (ref "C73") (pin "2") (pinfunction "2_2") (pintype "passive"))
      (node (ref "IC15") (pin "D1") (pinfunction "VOUT1_1_D1") (pintype "power_in"))
      (node (ref "IC15") (pin "E1") (pinfunction "VOUT1_2_E1") (pintype "power_in"))
      (node (ref "L2") (pin "1") (pinfunction "1_1") (pintype "passive"))
    )
    (net (code "25") (name "Net-(IC15-VOUT2_1)") (class "Default")
      (node (ref "C161") (pin "2") (pinfunction "2_2") (pintype "passive"))
      (node (ref "IC15") (pin "A1") (pinfunction "VOUT2_1_A1") (pintype "power_in"))
      (node (ref "IC15") (pin "B1") (pinfunction "VOUT2_2_B1") (pintype "power_in"))
      (node (ref "L3") (pin "1") (pinfunction "1_1") (pintype "passive"))
    )
    (net (code "26") (name "Net-(IC18-FB)") (class "Default")
      (node (ref "IC18") (pin "16") (pinfunction "FB_16") (pintype "input"))
      (node (ref "R129") (pin "1") (pinfunction "1_1") (pintype "passive"))
      (node (ref "R130") (pin "2") (pinfunction "2_2") (pintype "passive"))
    )
    (net (code "27") (name "Net-(IC20-ADJ)") (class "Default")
      (node (ref "IC20") (pin "4") (pinfunction "ADJ_4") (pintype "input"))
      (node (ref "R131") (pin "1") (pinfunction "1_1") (pintype "passive"))
      (node (ref "R132") (pin "2") (pinfunction "2_2") (pintype "passive"))
    )
    (net (code "28") (name "Net-(IC20-BYP)") (class "Default")
      (node (ref "C170") (pin "1") (pinfunction "1_1") (pintype "passive"))
      (node (ref "IC20") (pin "3") (pinfunction "BYP_3") (pintype "input"))
    )
    (net (code "29") (name "Net-(IC21-SET)") (class "Default")
      (node (ref "C174") (pin "1") (pinfunction "1_1") (pintype "passive"))
      (node (ref "IC21") (pin "7") (pinfunction "SET_7") (pintype "input"))
      (node (ref "R133") (pin "2") (pinfunction "2_2") (pintype "passive"))
    )
    (net (code "30") (name "Net-(IC22-FB)") (class "Default")
      (node (ref "IC22") (pin "5") (pinfunction "FB_5") (pintype "input"))
      (node (ref "R134") (pin "1") (pinfunction "1_1") (pintype "passive"))
      (node (ref "R136") (pin "2") (pinfunction "2_2") (pintype "passive"))
    )
    (net (code "31") (name "Net-(IC22-MODE)") (class "Default")
      (node (ref "IC22") (pin "10") (pinfunction "MODE_10") (pintype "input"))
      (node (ref "R166") (pin "1") (pinfunction "1_1") (pintype "passive"))
    )
    (net (code "32") (name "Net-(IC22-SS{slash}TR)") (class "Default")
      (node (ref "C139") (pin "1") (pinfunction "1_1") (pintype "passive"))
      (node (ref "IC22") (pin "9") (pinfunction "SS/TR_9") (pintype "input"))
    )
    (net (code "33") (name "Net-(IC22-SW)") (class "Default")
      (node (ref "IC22") (pin "2") (pinfunction "SW_2") (pintype "output"))
      (node (ref "L4") (pin "1") (pinfunction "1_1") (pintype "passive"))
    )
    (net (code "34") (name "Net-(LD1-A)") (class "Default")
      (node (ref "LD1") (pin "2") (pinfunction "A_2") (pintype "passive"))
      (node (ref "R5") (pin "1") (pinfunction "1_1") (pintype "passive"))
    )
    (net (code "35") (name "Net-(LD7B-A)") (class "Default")
      (node (ref "LD7") (pin "4") (pinfunction "A_4") (pintype "passive"))
      (node (ref "R143") (pin "1") (pinfunction "1_1") (pintype "passive"))
    )
    (net (code "36") (name "Net-(LD9-A)") (class "Default")
      (node (ref "LD9") (pin "2") (pinfunction "A_2") (pintype "passive"))
      (node (ref "R139") (pin "1") (pinfunction "1_1") (pintype "passive"))
    )
    (net (code "37") (name "Net-(R84-Pad2)") (class "Default")
      (node (ref "R84") (pin "2") (pinfunction "2_2") (pintype "passive"))
      (node (ref "R87") (pin "1") (pinfunction "1_1") (pintype "passive"))
    )
    (net (code "38") (name "Net-(R133-Pad1)") (class "Default")
      (node (ref "R133") (pin "1") (pinfunction "1_1") (pintype "passive"))
      (node (ref "R135") (pin "2") (pinfunction "2_2") (pintype "passive"))
    )
    (net (code "39") (name "P1V8A") (class "Default")
      (node (ref "C169") (pin "2") (pinfunction "2_2") (pintype "passive"))
      (node (ref "IC18") (pin "1") (pinfunction "OUT_1") (pintype "power_in"))
      (node (ref "IC18") (pin "18") (pinfunction "OUT_18") (pintype "power_in"))
      (node (ref "IC18") (pin "19") (pinfunction "OUT_19") (pintype "power_in"))
      (node (ref "IC18") (pin "20") (pinfunction "OUT_20") (pintype "power_in"))
      (node (ref "R129") (pin "2") (pinfunction "2_2") (pintype "passive"))
    )
    (net (code "40") (name "P2V1") (class "Default")
      (node (ref "C163") (pin "2") (pinfunction "2_2") (pintype "passive"))
      (node (ref "C167") (pin "1") (pinfunction "1_1") (pintype "passive"))
      (node (ref "C76") (pin "1") (pinfunction "1_1") (pintype "passive"))
      (node (ref "IC18") (pin "5") (pinfunction "IN_5") (pintype "input"))
      (node (ref "IC18") (pin "6") (pinfunction "IN_6") (pintype "input"))
      (node (ref "IC18") (pin "7") (pinfunction "IN_7") (pintype "input"))
      (node (ref "IC18") (pin "8") (pinfunction "IN_8") (pintype "input"))
      (node (ref "L3") (pin "2") (pinfunction "2_2") (pintype "passive"))
    )
    (net (code "41") (name "P3V3") (class "Default")
      (node (ref "C166") (pin "2") (pinfunction "2_2") (pintype "passive"))
      (node (ref "IC11") (pin "1") (pinfunction "OUT_1") (pintype "power_in"))
      (node (ref "IC11") (pin "18") (pinfunction "OUT_18") (pintype "power_in"))
      (node (ref "IC11") (pin "19") (pinfunction "OUT_19") (pintype "power_in"))
      (node (ref "IC11") (pin "20") (pinfunction "OUT_20") (pintype "power_in"))
      (node (ref "R118") (pin "2") (pinfunction "2_2") (pintype "passive"))
    )
    (net (code "42") (name "P3V3A") (class "Default")
      (node (ref "C78") (pin "2") (pinfunction "2_2") (pintype "passive"))
      (node (ref "IC7") (pin "1") (pinfunction "OUT_1") (pintype "power_in"))
      (node (ref "IC7") (pin "18") (pinfunction "OUT_18") (pintype "power_in"))
      (node (ref "IC7") (pin "19") (pinfunction "OUT_19") (pintype "power_in"))
      (node (ref "IC7") (pin "20") (pinfunction "OUT_20") (pintype "power_in"))
      (node (ref "R23") (pin "2") (pinfunction "2_2") (pintype "passive"))
    )
    (net (code "43") (name "P3V3_MP") (class "Default")
      (node (ref "C48") (pin "2") (pinfunction "2_2") (pintype "passive"))
      (node (ref "IC12") (pin "8") (pinfunction "+VS_8") (pintype "power_in"))
      (node (ref "R120") (pin "1") (pinfunction "1_1") (pintype "passive"))
      (node (ref "R121") (pin "2") (pinfunction "2_2") (pintype "passive"))
      (node (ref "R122") (pin "2") (pinfunction "2_2") (pintype "passive"))
      (node (ref "R143") (pin "2") (pinfunction "2_2") (pintype "passive"))
    )
    (net (code "44") (name "P3V6") (class "Default")
      (node (ref "C160") (pin "1") (pinfunction "1_1") (pintype "passive"))
      (node (ref "C63") (pin "1") (pinfunction "1_1") (pintype "passive"))
      (node (ref "C74") (pin "1") (pinfunction "1_1") (pintype "passive"))
      (node (ref "C75") (pin "2") (pinfunction "2_2") (pintype "passive"))
      (node (ref "IC11") (pin "5") (pinfunction "IN_5") (pintype "input"))
      (node (ref "IC11") (pin "6") (pinfunction "IN_6") (pintype "input"))
      (node (ref "IC11") (pin "7") (pinfunction "IN_7") (pintype "input"))
      (node (ref "IC11") (pin "8") (pinfunction "IN_8") (pintype "input"))
      (node (ref "IC7") (pin "5") (pinfunction "IN_5") (pintype "input"))
      (node (ref "IC7") (pin "6") (pinfunction "IN_6") (pintype "input"))
      (node (ref "IC7") (pin "7") (pinfunction "IN_7") (pintype "input"))
      (node (ref "IC7") (pin "8") (pinfunction "IN_8") (pintype "input"))
      (node (ref "L2") (pin "2") (pinfunction "2_2") (pintype "passive"))
      (node (ref "R5") (pin "2") (pinfunction "2_2") (pintype "passive"))
    )
    (net (code "45") (name "P5V0A") (class "Default")
      (node (ref "C165") (pin "2") (pinfunction "2_2") (pintype "passive"))
      (node (ref "C168") (pin "2") (pinfunction "2_2") (pintype "passive"))
      (node (ref "C170") (pin "2") (pinfunction "2_2") (pintype "passive"))
      (node (ref "C173") (pin "2") (pinfunction "2_2") (pintype "passive"))
      (node (ref "C77") (pin "2") (pinfunction "2_2") (pintype "passive"))
      (node (ref "C79") (pin "1") (pinfunction "1_1") (pintype "passive"))
      (node (ref "IC11") (pin "10") (pinfunction "BIAS_10") (pintype "input"))
      (node (ref "IC11") (pin "11") (pinfunction "EN_11") (pintype "input"))
      (node (ref "IC18") (pin "10") (pinfunction "BIAS_10") (pintype "input"))
      (node (ref "IC18") (pin "11") (pinfunction "EN_11") (pintype "input"))
      (node (ref "IC20") (pin "5") (pinfunction "OUT_5") (pintype "power_in"))
      (node (ref "IC7") (pin "10") (pinfunction "BIAS_10") (pintype "input"))
      (node (ref "IC7") (pin "11") (pinfunction "EN_11") (pintype "input"))
      (node (ref "R131") (pin "2") (pinfunction "2_2") (pintype "passive"))
      (node (ref "R139") (pin "2") (pinfunction "2_2") (pintype "passive"))
    )
    (net (code "46") (name "P7V0A") (class "Default")
      (node (ref "C155") (pin "2") (pinfunction "2_2") (pintype "passive"))
      (node (ref "C177") (pin "2") (pinfunction "2_2") (pintype "passive"))
      (node (ref "IC21") (pin "10") (pinfunction "OUT_10") (pintype "output"))
      (node (ref "IC21") (pin "9") (pinfunction "OUTS_9") (pintype "output"))
    )
    (net (code "47") (name "P7V5") (class "Default")
      (node (ref "C178") (pin "2") (pinfunction "2_2") (pintype "passive"))
      (node (ref "C179") (pin "2") (pinfunction "2_2") (pintype "passive"))
      (node (ref "C211") (pin "2") (pinfunction "2_2") (pintype "passive"))
      (node (ref "IC22") (pin "6") (pinfunction "VOS_6") (pintype "input"))
      (node (ref "L4") (pin "2") (pinfunction "2_2") (pintype "passive"))
      (node (ref "L5") (pin "1") (pinfunction "1_1") (pintype "passive"))
      (node (ref "R134") (pin "2") (pinfunction "2_2") (pintype "passive"))
      (node (ref "R53") (pin "2") (pinfunction "2_2") (pintype "passive"))
    )
    (net (code "48") (name "P7V5A") (class "Default")
      (node (ref "C132") (pin "2") (pinfunction "2_2") (pintype "passive"))
      (node (ref "C156") (pin "1") (pinfunction "1_1") (pintype "passive"))
      (node (ref "C171") (pin "2") (pinfunction "2_2") (pintype "passive"))
      (node (ref "C183") (pin "2") (pinfunction "2_2") (pintype "passive"))
      (node (ref "IC20") (pin "1") (pinfunction "IN_1") (pintype "input"))
      (node (ref "IC21") (pin "1") (pinfunction "IN_1") (pintype "input"))
      (node (ref "IC21") (pin "2") (pinfunction "IN_2") (pintype "input"))
      (node (ref "IC21") (pin "3") (pinfunction "EN/UV_3") (pintype "input"))
      (node (ref "IC21") (pin "6") (pinfunction "PGFB_6") (pintype "input"))
      (node (ref "L5") (pin "2") (pinfunction "2_2") (pintype "passive"))
    )
    (net (code "49") (name "P12V0") (class "Default")
      (node (ref "C181") (pin "2") (pinfunction "2_2") (pintype "passive"))
      (node (ref "C182") (pin "2") (pinfunction "2_2") (pintype "passive"))
      (node (ref "C64") (pin "2") (pinfunction "2_2") (pintype "passive"))
      (node (ref "C70") (pin "2") (pinfunction "2_2") (pintype "passive"))
      (node (ref "D3") (pin "1") (pinfunction "C_1") (pintype "passive"))
      (node (ref "FL1") (pin "2") (pinfunction "CB_2") (pintype "passive"))
      (node (ref "IC15") (pin "A2") (pinfunction "VIN_1_A2") (pintype "power_in"))
      (node (ref "IC15") (pin "B3") (pinfunction "VIN_2_B3") (pintype "power_in"))
      (node (ref "IC15") (pin "D3") (pinfunction "VIN_3_D3") (pintype "power_in"))
      (node (ref "IC15") (pin "E2") (pinfunction "VIN_4_E2") (pintype "power_in"))
      (node (ref "IC22") (pin "1") (pinfunction "VIN_1") (pintype "input"))
      (node (ref "IC22") (pin "8") (pinfunction "EN_8") (pintype "input"))
      (node (ref "R166") (pin "2") (pinfunction "2_2") (pintype "passive"))
    )
    (net (code "50") (name "unconnected-(IC7-NC-Pad2)") (class "Default")
      (node (ref "IC7") (pin "2") (pinfunction "NC_2") (pintype "passive+no_connect"))
    )
    (net (code "51") (name "unconnected-(IC7-NC-Pad3)") (class "Default")
      (node (ref "IC7") (pin "3") (pinfunction "NC_3") (pintype "passive+no_connect"))
    )
    (net (code "52") (name "unconnected-(IC7-NC-Pad4)") (class "Default")
      (node (ref "IC7") (pin "4") (pinfunction "NC_4") (pintype "passive+no_connect"))
    )
    (net (code "53") (name "unconnected-(IC7-NC-Pad13)") (class "Default")
      (node (ref "IC7") (pin "13") (pinfunction "NC_13") (pintype "passive+no_connect"))
    )
    (net (code "54") (name "unconnected-(IC7-NC-Pad14)") (class "Default")
      (node (ref "IC7") (pin "14") (pinfunction "NC_14") (pintype "passive+no_connect"))
    )
    (net (code "55") (name "unconnected-(IC7-NC-Pad17)") (class "Default")
      (node (ref "IC7") (pin "17") (pinfunction "NC_17") (pintype "passive+no_connect"))
    )
    (net (code "56") (name "unconnected-(IC7-SS-Pad15)") (class "Default")
      (node (ref "IC7") (pin "15") (pinfunction "SS_15") (pintype "output+no_connect"))
    )
    (net (code "57") (name "unconnected-(IC11-NC-Pad2)") (class "Default")
      (node (ref "IC11") (pin "2") (pinfunction "NC_2") (pintype "passive+no_connect"))
    )
    (net (code "58") (name "unconnected-(IC11-NC-Pad3)") (class "Default")
      (node (ref "IC11") (pin "3") (pinfunction "NC_3") (pintype "passive+no_connect"))
    )
    (net (code "59") (name "unconnected-(IC11-NC-Pad4)") (class "Default")
      (node (ref "IC11") (pin "4") (pinfunction "NC_4") (pintype "passive+no_connect"))
    )
    (net (code "60") (name "unconnected-(IC11-NC-Pad13)") (class "Default")
      (node (ref "IC11") (pin "13") (pinfunction "NC_13") (pintype "passive+no_connect"))
    )
    (net (code "61") (name "unconnected-(IC11-NC-Pad14)") (class "Default")
      (node (ref "IC11") (pin "14") (pinfunction "NC_14") (pintype "passive+no_connect"))
    )
    (net (code "62") (name "unconnected-(IC11-NC-Pad17)") (class "Default")
      (node (ref "IC11") (pin "17") (pinfunction "NC_17") (pintype "passive+no_connect"))
    )
    (net (code "63") (name "unconnected-(IC11-SS-Pad15)") (class "Default")
      (node (ref "IC11") (pin "15") (pinfunction "SS_15") (pintype "output+no_connect"))
    )
    (net (code "64") (name "unconnected-(IC18-NC-Pad2)") (class "Default")
      (node (ref "IC18") (pin "2") (pinfunction "NC_2") (pintype "passive+no_connect"))
    )
    (net (code "65") (name "unconnected-(IC18-NC-Pad3)") (class "Default")
      (node (ref "IC18") (pin "3") (pinfunction "NC_3") (pintype "passive+no_connect"))
    )
    (net (code "66") (name "unconnected-(IC18-NC-Pad4)") (class "Default")
      (node (ref "IC18") (pin "4") (pinfunction "NC_4") (pintype "passive+no_connect"))
    )
    (net (code "67") (name "unconnected-(IC18-NC-Pad13)") (class "Default")
      (node (ref "IC18") (pin "13") (pinfunction "NC_13") (pintype "passive+no_connect"))
    )
    (net (code "68") (name "unconnected-(IC18-NC-Pad14)") (class "Default")
      (node (ref "IC18") (pin "14") (pinfunction "NC_14") (pintype "passive+no_connect"))
    )
    (net (code "69") (name "unconnected-(IC18-NC-Pad17)") (class "Default")
      (node (ref "IC18") (pin "17") (pinfunction "NC_17") (pintype "passive+no_connect"))
    )
    (net (code "70") (name "unconnected-(IC18-SS-Pad15)") (class "Default")
      (node (ref "IC18") (pin "15") (pinfunction "SS_15") (pintype "output+no_connect"))
    )
    (net (code "71") (name "unconnected-(IC21-PG-Pad4)") (class "Default")
      (node (ref "IC21") (pin "4") (pinfunction "PG_4") (pintype "output+no_connect"))
    )
  )
)
